# OPNpool_r2.net
KiCad netlist of a schematic drawn in EAGLE
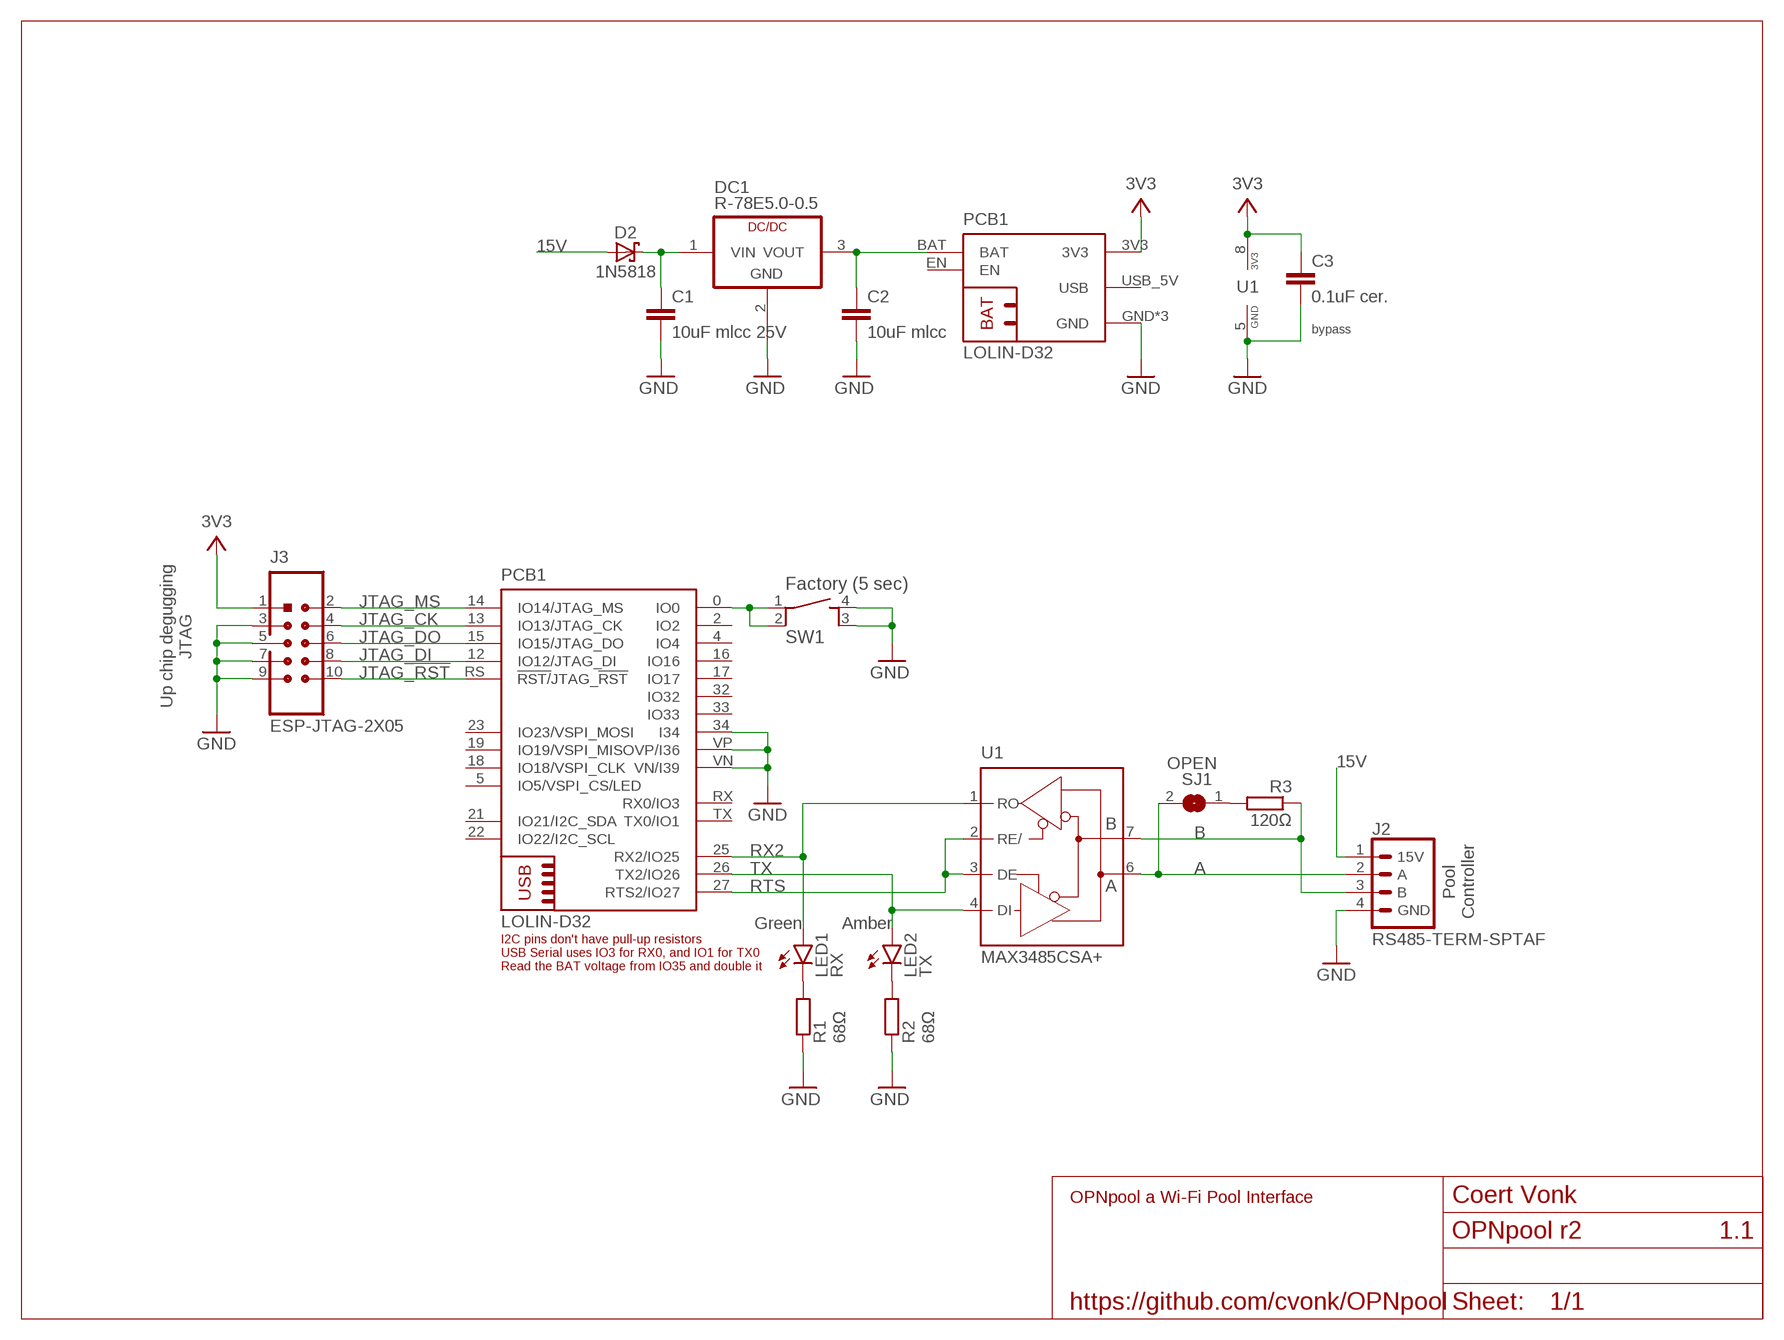
[diagram p0: schematic, sheet 1]

(export (version "E")
  (design (tool "Eeschema 10.0.6"))
  (components
    (comp (ref "C1")
      (value "10uF mlcc 25V")
      (footprint "eagle-import:C0805K")
      (fields (field (name "MANF") "Murata Electronics"))
      (libsource (lib "eagle-import") (part "C-EUC0805K"))
    )
    (comp (ref "C2")
      (value "10uF mlcc")
      (footprint "eagle-import:C0805K")
      (fields (field (name "MANF") "Murata Electronics"))
      (libsource (lib "eagle-import") (part "C-EUC0805K"))
    )
    (comp (ref "C3")
      (value "0.1uF cer.")
      (footprint "eagle-import:C0805K")
      (fields (field (name "MANF") "KEMET"))
      (libsource (lib "eagle-import") (part "C-EUC0805K"))
    )
    (comp (ref "D2")
      (value "1N5818")
      (footprint "eagle-import:DO41-7.6")
      (fields (field (name "MANF") "Rectron"))
      (libsource (lib "eagle-import") (part "1N5818"))
    )
    (comp (ref "DC1")
      (value "R-78E5.0-0.5")
      (footprint "eagle-import:SIP3")
      (fields (field (name "MANF") "RECOM Power"))
      (libsource (lib "eagle-import") (part "R-78E-0.55.0"))
    )
    (comp (ref "J2")
      (value "RS485-TERM-SPTAF")
      (footprint "eagle-import:SPTAF1_4-5,0-LL")
      (fields (field (name "MANF") "Phoenix Contact"))
      (libsource (lib "eagle-import") (part "RS485-TERM-SPTAF"))
    )
    (comp (ref "J3")
      (value "ESP-JTAG-2X05")
      (footprint "eagle-import:2X05_SHROUDED")
      (fields (field (name "MANF") "Molex"))
      (libsource (lib "eagle-import") (part "ESP-JTAG-2X05"))
    )
    (comp (ref "LED1")
      (value "RX")
      (footprint "eagle-import:CHIPLED_0805")
      (libsource (lib "eagle-import") (part "LEDCHIPLED_0805"))
    )
    (comp (ref "LED2")
      (value "TX")
      (footprint "eagle-import:CHIPLED_0805")
      (libsource (lib "eagle-import") (part "LEDCHIPLED_0805"))
    )
    (comp (ref "PCB1")
      (value "LOLIN-D32")
      (footprint "eagle-import:LOLIN-D32")
      (fields
        (field (name "MANF") "WEMOS Electronics")
        (field (name "ALIEXPRESS#") "32808551116")
        (field (name "MANF#") "D32")
      )
      (libsource (lib "eagle-import") (part "LOLIN-D32"))
    )
    (comp (ref "R1")
      (value "68Ω")
      (footprint "eagle-import:R0805")
      (fields (field (name "MANF") "Bourns"))
      (libsource (lib "eagle-import") (part "R-EU_R0805"))
    )
    (comp (ref "R2")
      (value "68Ω")
      (footprint "eagle-import:R0805")
      (fields (field (name "MANF") "Bourns"))
      (libsource (lib "eagle-import") (part "R-EU_R0805"))
    )
    (comp (ref "R3")
      (value "120Ω")
      (footprint "eagle-import:R0805")
      (fields (field (name "MANF") "Bourns"))
      (libsource (lib "eagle-import") (part "R-EU_R0805"))
    )
    (comp (ref "SJ1")
      (value "OPEN")
      (footprint "eagle-import:SJ")
      (libsource (lib "eagle-import") (part "SJ"))
    )
    (comp (ref "SW1")
      (value "Factory (5 sec)")
      (footprint "eagle-import:TE_1-1825910-4")
      (fields
        (field (name "COMMENT") "1-1825910-4")
        (field (name "DIGI-KEY_PART_NUMBER") "450-1653-ND")
        (field (name "MF") "TE Connectivity")
      )
      (libsource (lib "eagle-import") (part "1-1825910-4"))
    )
    (comp (ref "U1")
      (value "MAX3485CSA+")
      (footprint "eagle-import:SO08")
      (fields
        (field (name "MF") "MAXIM")
        (field (name "MPN") "MAX481CSA")
        (field (name "MANF") "Maxim Integrated")
        (field (name "MANF#") "MAX3485CSA+")
        (field (name "MOUSER#") "700-MAX3485CSA")
      )
      (libsource (lib "eagle-import") (part "MAX3485CSA+"))
    )
  )
  (nets
    (net (code "1") (name "/15V") (class "Default")
      (node (ref "D2") (pin "A") (pinfunction "A_A") (pintype "passive"))
      (node (ref "J2") (pin "1") (pinfunction "15V_1") (pintype "power_in"))
    )
    (net (code "2") (name "/A") (class "Default")
      (node (ref "J2") (pin "2") (pinfunction "A_2") (pintype "passive"))
      (node (ref "SJ1") (pin "2") (pinfunction "2_2") (pintype "passive"))
      (node (ref "U1") (pin "6") (pinfunction "A_6") (pintype "passive"))
    )
    (net (code "3") (name "/B") (class "Default")
      (node (ref "J2") (pin "3") (pinfunction "B_3") (pintype "passive"))
      (node (ref "R3") (pin "1") (pinfunction "1_1") (pintype "passive"))
      (node (ref "U1") (pin "7") (pinfunction "B_7") (pintype "passive"))
    )
    (net (code "4") (name "/JTAG_CK") (class "Default")
      (node (ref "J3") (pin "4") (pinfunction "TCK_4") (pintype "passive"))
      (node (ref "PCB1") (pin "13") (pinfunction "IO13/JTAG_CK_13") (pintype "bidirectional"))
    )
    (net (code "5") (name "/JTAG_DI") (class "Default")
      (node (ref "J3") (pin "8") (pinfunction "TDI_8") (pintype "passive"))
      (node (ref "PCB1") (pin "12") (pinfunction "IO12/JTAG_DI_12") (pintype "bidirectional"))
    )
    (net (code "6") (name "/JTAG_DO") (class "Default")
      (node (ref "J3") (pin "6") (pinfunction "TDO_6") (pintype "passive"))
      (node (ref "PCB1") (pin "15") (pinfunction "IO15/JTAG_DO_15") (pintype "bidirectional"))
    )
    (net (code "7") (name "/JTAG_MS") (class "Default")
      (node (ref "J3") (pin "2") (pinfunction "TMS_2") (pintype "passive"))
      (node (ref "PCB1") (pin "14") (pinfunction "IO14/JTAG_MS_14") (pintype "bidirectional"))
    )
    (net (code "8") (name "/JTAG_~{RST}") (class "Default")
      (node (ref "J3") (pin "10") (pinfunction "NC_10") (pintype "passive"))
      (node (ref "PCB1") (pin "RS") (pinfunction "~{RST/}JTAG_~{RST}_RS") (pintype "input"))
    )
    (net (code "9") (name "/RTS") (class "Default")
      (node (ref "PCB1") (pin "27") (pinfunction "RTS2/IO27_27") (pintype "bidirectional"))
      (node (ref "U1") (pin "2") (pinfunction "RE/_2") (pintype "input"))
      (node (ref "U1") (pin "3") (pinfunction "DE_3") (pintype "input"))
    )
    (net (code "10") (name "/RX2") (class "Default")
      (node (ref "LED1") (pin "A") (pinfunction "A_A") (pintype "passive"))
      (node (ref "PCB1") (pin "25") (pinfunction "RX2/IO25_25") (pintype "bidirectional"))
      (node (ref "U1") (pin "1") (pinfunction "RO_1") (pintype "output"))
    )
    (net (code "11") (name "/TX") (class "Default")
      (node (ref "LED2") (pin "A") (pinfunction "A_A") (pintype "passive"))
      (node (ref "PCB1") (pin "26") (pinfunction "TX2/IO26_26") (pintype "bidirectional"))
      (node (ref "U1") (pin "4") (pinfunction "DI_4") (pintype "input"))
    )
    (net (code "12") (name "/USB") (class "Default")
      (node (ref "PCB1") (pin "USB_5V") (pinfunction "USB_USB_5V") (pintype "power_in"))
    )
    (net (code "13") (name "3V3") (class "Default")
      (node (ref "C3") (pin "1") (pinfunction "1_1") (pintype "passive"))
      (node (ref "J3") (pin "1") (pinfunction "3V3_1") (pintype "power_in"))
      (node (ref "PCB1") (pin "3V3") (pinfunction "3V3_3V3") (pintype "power_in"))
      (node (ref "U1") (pin "8") (pinfunction "VCC_8") (pintype "passive"))
    )
    (net (code "14") (name "GND") (class "Default")
      (node (ref "C1") (pin "2") (pinfunction "2_2") (pintype "passive"))
      (node (ref "C2") (pin "2") (pinfunction "2_2") (pintype "passive"))
      (node (ref "C3") (pin "2") (pinfunction "2_2") (pintype "passive"))
      (node (ref "DC1") (pin "2") (pinfunction "GND_2") (pintype "power_in"))
      (node (ref "J2") (pin "4") (pinfunction "GND_4") (pintype "power_in"))
      (node (ref "J3") (pin "3") (pinfunction "GND_3") (pintype "power_in"))
      (node (ref "J3") (pin "5") (pinfunction "GND_5") (pintype "power_in"))
      (node (ref "J3") (pin "7") (pinfunction "GND_7") (pintype "power_in"))
      (node (ref "J3") (pin "9") (pinfunction "GND_9") (pintype "power_in"))
      (node (ref "PCB1") (pin "34") (pinfunction "I34_34") (pintype "input"))
      (node (ref "PCB1") (pin "GND") (pinfunction "GND_GND") (pintype "power_in"))
      (node (ref "PCB1") (pin "GND@1") (pinfunction "GND_GND@1") (pintype "power_in"))
      (node (ref "PCB1") (pin "GND@2") (pinfunction "GND_GND@2") (pintype "power_in"))
      (node (ref "PCB1") (pin "VN") (pinfunction "VN/I39_VN") (pintype "input"))
      (node (ref "PCB1") (pin "VP") (pinfunction "VP/I36_VP") (pintype "input"))
      (node (ref "R1") (pin "1") (pinfunction "1_1") (pintype "passive"))
      (node (ref "R2") (pin "1") (pinfunction "1_1") (pintype "passive"))
      (node (ref "SW1") (pin "3") (pinfunction "3_3") (pintype "passive"))
      (node (ref "SW1") (pin "4") (pinfunction "4_4") (pintype "passive"))
      (node (ref "U1") (pin "5") (pinfunction "GND_5") (pintype "power_in"))
    )
    (net (code "15") (name "Net-(DC1-VIN)") (class "Default")
      (node (ref "C1") (pin "1") (pinfunction "1_1") (pintype "passive"))
      (node (ref "D2") (pin "C") (pinfunction "C_C") (pintype "passive"))
      (node (ref "DC1") (pin "1") (pinfunction "VIN_1") (pintype "power_in"))
    )
    (net (code "16") (name "Net-(DC1-VOUT)") (class "Default")
      (node (ref "C2") (pin "1") (pinfunction "1_1") (pintype "passive"))
      (node (ref "DC1") (pin "3") (pinfunction "VOUT_3") (pintype "power_in"))
      (node (ref "PCB1") (pin "BAT") (pinfunction "BAT_BAT") (pintype "power_in"))
    )
    (net (code "17") (name "Net-(LED1-PadC)") (class "Default")
      (node (ref "LED1") (pin "C") (pinfunction "C_C") (pintype "passive"))
      (node (ref "R1") (pin "2") (pinfunction "2_2") (pintype "passive"))
    )
    (net (code "18") (name "Net-(LED2-PadC)") (class "Default")
      (node (ref "LED2") (pin "C") (pinfunction "C_C") (pintype "passive"))
      (node (ref "R2") (pin "2") (pinfunction "2_2") (pintype "passive"))
    )
    (net (code "19") (name "Net-(PCB1A-IO0)") (class "Default")
      (node (ref "PCB1") (pin "0") (pinfunction "IO0_0") (pintype "bidirectional"))
      (node (ref "SW1") (pin "1") (pinfunction "1_1") (pintype "passive"))
      (node (ref "SW1") (pin "2") (pinfunction "2_2") (pintype "passive"))
    )
    (net (code "20") (name "Net-(R3-Pad2)") (class "Default")
      (node (ref "R3") (pin "2") (pinfunction "2_2") (pintype "passive"))
      (node (ref "SJ1") (pin "1") (pinfunction "1_1") (pintype "passive"))
    )
    (net (code "21") (name "unconnected-(PCB1-PadEN)") (class "Default")
      (node (ref "PCB1") (pin "EN") (pinfunction "EN_EN") (pintype "passive"))
    )
    (net (code "22") (name "unconnected-(PCB1A-IO2-Pad2)") (class "Default")
      (node (ref "PCB1") (pin "2") (pinfunction "IO2_2") (pintype "bidirectional"))
    )
    (net (code "23") (name "unconnected-(PCB1A-IO4-Pad4)") (class "Default")
      (node (ref "PCB1") (pin "4") (pinfunction "IO4_4") (pintype "bidirectional"))
    )
    (net (code "24") (name "unconnected-(PCB1A-IO5{slash}VSPI_CS{slash}LED-Pad5)") (class "Default")
      (node (ref "PCB1") (pin "5") (pinfunction "IO5/VSPI_CS/LED_5") (pintype "bidirectional"))
    )
    (net (code "25") (name "unconnected-(PCB1A-IO16-Pad16)") (class "Default")
      (node (ref "PCB1") (pin "16") (pinfunction "IO16_16") (pintype "bidirectional"))
    )
    (net (code "26") (name "unconnected-(PCB1A-IO17-Pad17)") (class "Default")
      (node (ref "PCB1") (pin "17") (pinfunction "IO17_17") (pintype "bidirectional"))
    )
    (net (code "27") (name "unconnected-(PCB1A-IO18{slash}VSPI_CLK-Pad18)") (class "Default")
      (node (ref "PCB1") (pin "18") (pinfunction "IO18/VSPI_CLK_18") (pintype "bidirectional"))
    )
    (net (code "28") (name "unconnected-(PCB1A-IO19{slash}VSPI_MISO-Pad19)") (class "Default")
      (node (ref "PCB1") (pin "19") (pinfunction "IO19/VSPI_MISO_19") (pintype "bidirectional"))
    )
    (net (code "29") (name "unconnected-(PCB1A-IO21{slash}I2C_SDA-Pad21)") (class "Default")
      (node (ref "PCB1") (pin "21") (pinfunction "IO21/I2C_SDA_21") (pintype "bidirectional"))
    )
    (net (code "30") (name "unconnected-(PCB1A-IO22{slash}I2C_SCL-Pad22)") (class "Default")
      (node (ref "PCB1") (pin "22") (pinfunction "IO22/I2C_SCL_22") (pintype "bidirectional"))
    )
    (net (code "31") (name "unconnected-(PCB1A-IO23{slash}VSPI_MOSI-Pad23)") (class "Default")
      (node (ref "PCB1") (pin "23") (pinfunction "IO23/VSPI_MOSI_23") (pintype "bidirectional"))
    )
    (net (code "32") (name "unconnected-(PCB1A-IO32-Pad32)") (class "Default")
      (node (ref "PCB1") (pin "32") (pinfunction "IO32_32") (pintype "bidirectional"))
    )
    (net (code "33") (name "unconnected-(PCB1A-IO33-Pad33)") (class "Default")
      (node (ref "PCB1") (pin "33") (pinfunction "IO33_33") (pintype "bidirectional"))
    )
    (net (code "34") (name "unconnected-(PCB1A-RX0{slash}IO3-PadRX)") (class "Default")
      (node (ref "PCB1") (pin "RX") (pinfunction "RX0/IO3_RX") (pintype "bidirectional"))
    )
    (net (code "35") (name "unconnected-(PCB1A-TX0{slash}IO1-PadTX)") (class "Default")
      (node (ref "PCB1") (pin "TX") (pinfunction "TX0/IO1_TX") (pintype "bidirectional"))
    )
  )
)
